# 7_RK3399_MIPI-CSI_I2C.net
KiCad netlist of a schematic drawn in Altium Designer
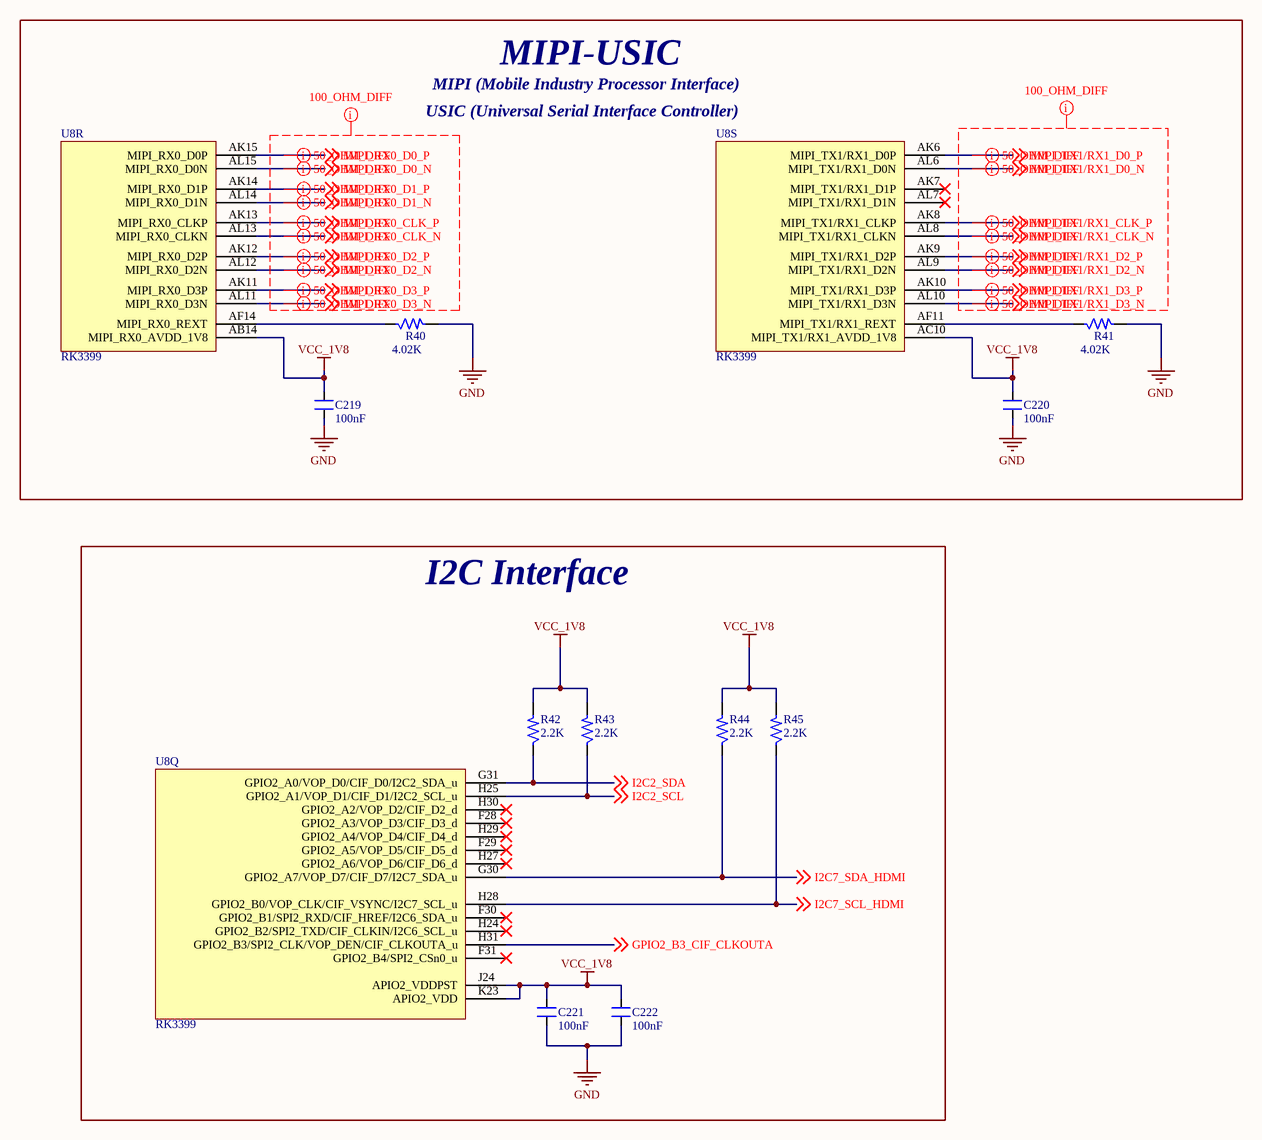
[diagram p0: [7] RK3399_MIPI-CSI_I2C.SchDoc]

(export (version "E")
  (design (tool "Eeschema 10.0.6"))
  (components
    (comp (ref "C219")
      (value "100nF")
      (footprint "CAP_0201")
      (description "0.1µF ±10% 25V Ceramic Capacitor X5R 0201 (0603 Metric)")
      (fields
        (field (name "MANUFACTURER") "TDK Corporation")
        (field (name "MANUFACTURER PART NUMBER") "C0603X5R1E104K030BB")
      )
      (libsource (lib "EsteemPCB_SOM_Course_intlib") (part "CAP_100nF-25V-10%-0201"))
    )
    (comp (ref "C220")
      (value "100nF")
      (footprint "CAP_0201")
      (description "0.1µF ±10% 25V Ceramic Capacitor X5R 0201 (0603 Metric)")
      (fields
        (field (name "MANUFACTURER") "TDK Corporation")
        (field (name "MANUFACTURER PART NUMBER") "C0603X5R1E104K030BB")
      )
      (libsource (lib "EsteemPCB_SOM_Course_intlib") (part "CAP_100nF-25V-10%-0201"))
    )
    (comp (ref "C221")
      (value "100nF")
      (footprint "CAP_0201")
      (description "0.1µF ±10% 25V Ceramic Capacitor X5R 0201 (0603 Metric)")
      (fields
        (field (name "MANUFACTURER") "TDK Corporation")
        (field (name "MANUFACTURER PART NUMBER") "C0603X5R1E104K030BB")
      )
      (libsource (lib "EsteemPCB_SOM_Course_intlib") (part "CAP_100nF-25V-10%-0201"))
    )
    (comp (ref "C222")
      (value "100nF")
      (footprint "CAP_0201")
      (description "0.1µF ±10% 25V Ceramic Capacitor X5R 0201 (0603 Metric)")
      (fields
        (field (name "MANUFACTURER") "TDK Corporation")
        (field (name "MANUFACTURER PART NUMBER") "C0603X5R1E104K030BB")
      )
      (libsource (lib "EsteemPCB_SOM_Course_intlib") (part "CAP_100nF-25V-10%-0201"))
    )
    (comp (ref "R40")
      (value "4.02K")
      (footprint "RES_0201")
      (description "4.02 kOhms ±1% 0.05W, 1/20W Chip Resistor 0201 (0603 Metric) Thick Film")
      (fields
        (field (name "MANUFACTURER") "Yageo")
        (field (name "MANUFACTURER PART NUMBER") "RC0201FR-074K02L")
      )
      (libsource (lib "EsteemPCB_SOM_Course_intlib") (part "RES_4.02K-0.05W-1%-0201"))
    )
    (comp (ref "R41")
      (value "4.02K")
      (footprint "RES_0201")
      (description "4.02 kOhms ±1% 0.05W, 1/20W Chip Resistor 0201 (0603 Metric) Thick Film")
      (fields
        (field (name "MANUFACTURER") "Yageo")
        (field (name "MANUFACTURER PART NUMBER") "RC0201FR-074K02L")
      )
      (libsource (lib "EsteemPCB_SOM_Course_intlib") (part "RES_4.02K-0.05W-1%-0201"))
    )
    (comp (ref "R42")
      (value "2.2K")
      (footprint "RES_0201")
      (description "2.2 kOhms ±1% 0.05W, 1/20W Chip Resistor 0201 (0603 Metric) Thick Film")
      (fields
        (field (name "MANUFACTURER") "Stackpole Electronics Inc")
        (field (name "MANUFACTURER PART NUMBER") "RMCF0201FT2K20")
      )
      (libsource (lib "EsteemPCB_SOM_Course_intlib") (part "RES_2.2K-0.05W-1%-0201"))
    )
    (comp (ref "R43")
      (value "2.2K")
      (footprint "RES_0201")
      (description "2.2 kOhms ±1% 0.05W, 1/20W Chip Resistor 0201 (0603 Metric) Thick Film")
      (fields
        (field (name "MANUFACTURER") "Stackpole Electronics Inc")
        (field (name "MANUFACTURER PART NUMBER") "RMCF0201FT2K20")
      )
      (libsource (lib "EsteemPCB_SOM_Course_intlib") (part "RES_2.2K-0.05W-1%-0201"))
    )
    (comp (ref "R44")
      (value "2.2K")
      (footprint "RES_0201")
      (description "2.2 kOhms ±1% 0.05W, 1/20W Chip Resistor 0201 (0603 Metric) Thick Film")
      (fields
        (field (name "MANUFACTURER") "Stackpole Electronics Inc")
        (field (name "MANUFACTURER PART NUMBER") "RMCF0201FT2K20")
      )
      (libsource (lib "EsteemPCB_SOM_Course_intlib") (part "RES_2.2K-0.05W-1%-0201"))
    )
    (comp (ref "R45")
      (value "2.2K")
      (footprint "RES_0201")
      (description "2.2 kOhms ±1% 0.05W, 1/20W Chip Resistor 0201 (0603 Metric) Thick Film")
      (fields
        (field (name "MANUFACTURER") "Stackpole Electronics Inc")
        (field (name "MANUFACTURER PART NUMBER") "RMCF0201FT2K20")
      )
      (libsource (lib "EsteemPCB_SOM_Course_intlib") (part "RES_2.2K-0.05W-1%-0201"))
    )
    (comp (ref "U8")
      (value "RK3399")
      (footprint "FBGA828_23_826X826")
      (description "RK3399 is a low power, high performance processor for computing, personal mobile.")
      (fields (field (name "MANUFACTURER") "Rockchip"))
      (libsource (lib "EsteemPCB_SOM_Course_intlib") (part "IC_RK3399-FCBGA828"))
    )
  )
  (nets
    (net (code "1") (name "GND") (class "Default")
      (node (ref "C219") (pin "1") (pinfunction "1_1") (pintype "passive"))
      (node (ref "C220") (pin "1") (pinfunction "1_1") (pintype "passive"))
      (node (ref "C221") (pin "1") (pinfunction "1_1") (pintype "passive"))
      (node (ref "C222") (pin "1") (pinfunction "1_1") (pintype "passive"))
      (node (ref "R40") (pin "2") (pinfunction "2_2") (pintype "passive"))
      (node (ref "R41") (pin "2") (pinfunction "2_2") (pintype "passive"))
    )
    (net (code "2") (name "GPIO2_B3_CIF_CLKOUTA") (class "Default")
      (node (ref "U8") (pin "H31") (pinfunction "GPIO2_B3/SPI2_CLK/VOP_DEN/CIF_CLKOUTA_u_H31") (pintype "passive"))
    )
    (net (code "3") (name "I2C2_SCL") (class "Default")
      (node (ref "R43") (pin "1") (pinfunction "1_1") (pintype "passive"))
      (node (ref "U8") (pin "H25") (pinfunction "GPIO2_A1/VOP_D1/CIF_D1/I2C2_SCL_u_H25") (pintype "passive"))
    )
    (net (code "4") (name "I2C2_SDA") (class "Default")
      (node (ref "R42") (pin "1") (pinfunction "1_1") (pintype "passive"))
      (node (ref "U8") (pin "G31") (pinfunction "GPIO2_A0/VOP_D0/CIF_D0/I2C2_SDA_u_G31") (pintype "passive"))
    )
    (net (code "5") (name "I2C7_SCL_HDMI") (class "Default")
      (node (ref "R45") (pin "1") (pinfunction "1_1") (pintype "passive"))
      (node (ref "U8") (pin "H28") (pinfunction "GPIO2_B0/VOP_CLK/CIF_VSYNC/I2C7_SCL_u_H28") (pintype "passive"))
    )
    (net (code "6") (name "I2C7_SDA_HDMI") (class "Default")
      (node (ref "R44") (pin "1") (pinfunction "1_1") (pintype "passive"))
      (node (ref "U8") (pin "G30") (pinfunction "GPIO2_A7/VOP_D7/CIF_D7/I2C7_SDA_u_G30") (pintype "passive"))
    )
    (net (code "7") (name "MIPI_RX0_CLK_N") (class "Default")
      (node (ref "U8") (pin "AL13") (pinfunction "MIPI_RX0_CLKN_AL13") (pintype "passive"))
    )
    (net (code "8") (name "MIPI_RX0_CLK_P") (class "Default")
      (node (ref "U8") (pin "AK13") (pinfunction "MIPI_RX0_CLKP_AK13") (pintype "passive"))
    )
    (net (code "9") (name "MIPI_RX0_D0_N") (class "Default")
      (node (ref "U8") (pin "AL15") (pinfunction "MIPI_RX0_D0N_AL15") (pintype "passive"))
    )
    (net (code "10") (name "MIPI_RX0_D0_P") (class "Default")
      (node (ref "U8") (pin "AK15") (pinfunction "MIPI_RX0_D0P_AK15") (pintype "passive"))
    )
    (net (code "11") (name "MIPI_RX0_D1_N") (class "Default")
      (node (ref "U8") (pin "AL14") (pinfunction "MIPI_RX0_D1N_AL14") (pintype "passive"))
    )
    (net (code "12") (name "MIPI_RX0_D1_P") (class "Default")
      (node (ref "U8") (pin "AK14") (pinfunction "MIPI_RX0_D1P_AK14") (pintype "passive"))
    )
    (net (code "13") (name "MIPI_RX0_D2_N") (class "Default")
      (node (ref "U8") (pin "AL12") (pinfunction "MIPI_RX0_D2N_AL12") (pintype "passive"))
    )
    (net (code "14") (name "MIPI_RX0_D2_P") (class "Default")
      (node (ref "U8") (pin "AK12") (pinfunction "MIPI_RX0_D2P_AK12") (pintype "passive"))
    )
    (net (code "15") (name "MIPI_RX0_D3_N") (class "Default")
      (node (ref "U8") (pin "AL11") (pinfunction "MIPI_RX0_D3N_AL11") (pintype "passive"))
    )
    (net (code "16") (name "MIPI_RX0_D3_P") (class "Default")
      (node (ref "U8") (pin "AK11") (pinfunction "MIPI_RX0_D3P_AK11") (pintype "passive"))
    )
    (net (code "17") (name "MIPI_TX1{slash}RX1_CLK_N") (class "Default")
      (node (ref "U8") (pin "AL8") (pinfunction "MIPI_TX1/RX1_CLKN_AL8") (pintype "passive"))
    )
    (net (code "18") (name "MIPI_TX1{slash}RX1_CLK_P") (class "Default")
      (node (ref "U8") (pin "AK8") (pinfunction "MIPI_TX1/RX1_CLKP_AK8") (pintype "passive"))
    )
    (net (code "19") (name "MIPI_TX1{slash}RX1_D0_N") (class "Default")
      (node (ref "U8") (pin "AL6") (pinfunction "MIPI_TX1/RX1_D0N_AL6") (pintype "passive"))
    )
    (net (code "20") (name "MIPI_TX1{slash}RX1_D0_P") (class "Default")
      (node (ref "U8") (pin "AK6") (pinfunction "MIPI_TX1/RX1_D0P_AK6") (pintype "passive"))
    )
    (net (code "21") (name "MIPI_TX1{slash}RX1_D2_N") (class "Default")
      (node (ref "U8") (pin "AL9") (pinfunction "MIPI_TX1/RX1_D2N_AL9") (pintype "passive"))
    )
    (net (code "22") (name "MIPI_TX1{slash}RX1_D2_P") (class "Default")
      (node (ref "U8") (pin "AK9") (pinfunction "MIPI_TX1/RX1_D2P_AK9") (pintype "passive"))
    )
    (net (code "23") (name "MIPI_TX1{slash}RX1_D3_N") (class "Default")
      (node (ref "U8") (pin "AL10") (pinfunction "MIPI_TX1/RX1_D3N_AL10") (pintype "passive"))
    )
    (net (code "24") (name "MIPI_TX1{slash}RX1_D3_P") (class "Default")
      (node (ref "U8") (pin "AK10") (pinfunction "MIPI_TX1/RX1_D3P_AK10") (pintype "passive"))
    )
    (net (code "25") (name "Net-(U8R-MIPI_RX0_REXT)") (class "Default")
      (node (ref "R40") (pin "1") (pinfunction "1_1") (pintype "passive"))
      (node (ref "U8") (pin "AF14") (pinfunction "MIPI_RX0_REXT_AF14") (pintype "passive"))
    )
    (net (code "26") (name "Net-(U8S-MIPI_TX1{slash}RX1_REXT)") (class "Default")
      (node (ref "R41") (pin "1") (pinfunction "1_1") (pintype "passive"))
      (node (ref "U8") (pin "AF11") (pinfunction "MIPI_TX1/RX1_REXT_AF11") (pintype "passive"))
    )
    (net (code "27") (name "VCC_1V8") (class "Default")
      (node (ref "C219") (pin "2") (pinfunction "2_2") (pintype "passive"))
      (node (ref "C220") (pin "2") (pinfunction "2_2") (pintype "passive"))
      (node (ref "C221") (pin "2") (pinfunction "2_2") (pintype "passive"))
      (node (ref "C222") (pin "2") (pinfunction "2_2") (pintype "passive"))
      (node (ref "R42") (pin "2") (pinfunction "2_2") (pintype "passive"))
      (node (ref "R43") (pin "2") (pinfunction "2_2") (pintype "passive"))
      (node (ref "R44") (pin "2") (pinfunction "2_2") (pintype "passive"))
      (node (ref "R45") (pin "2") (pinfunction "2_2") (pintype "passive"))
      (node (ref "U8") (pin "AB14") (pinfunction "MIPI_RX0_AVDD_1V8_AB14") (pintype "passive"))
      (node (ref "U8") (pin "AC10") (pinfunction "MIPI_TX1/RX1_AVDD_1V8_AC10") (pintype "passive"))
      (node (ref "U8") (pin "J24") (pinfunction "APIO2_VDDPST_J24") (pintype "passive"))
      (node (ref "U8") (pin "K23") (pinfunction "APIO2_VDD_K23") (pintype "passive"))
    )
    (net (code "28") (name "unconnected-(U8Q-GPIO2_A2{slash}VOP_D2{slash}CIF_D2_d-PadH30)") (class "Default")
      (node (ref "U8") (pin "H30") (pinfunction "GPIO2_A2/VOP_D2/CIF_D2_d_H30") (pintype "passive+no_connect"))
    )
    (net (code "29") (name "unconnected-(U8Q-GPIO2_A3{slash}VOP_D3{slash}CIF_D3_d-PadF28)") (class "Default")
      (node (ref "U8") (pin "F28") (pinfunction "GPIO2_A3/VOP_D3/CIF_D3_d_F28") (pintype "passive+no_connect"))
    )
    (net (code "30") (name "unconnected-(U8Q-GPIO2_A4{slash}VOP_D4{slash}CIF_D4_d-PadH29)") (class "Default")
      (node (ref "U8") (pin "H29") (pinfunction "GPIO2_A4/VOP_D4/CIF_D4_d_H29") (pintype "passive+no_connect"))
    )
    (net (code "31") (name "unconnected-(U8Q-GPIO2_A5{slash}VOP_D5{slash}CIF_D5_d-PadF29)") (class "Default")
      (node (ref "U8") (pin "F29") (pinfunction "GPIO2_A5/VOP_D5/CIF_D5_d_F29") (pintype "passive+no_connect"))
    )
    (net (code "32") (name "unconnected-(U8Q-GPIO2_A6{slash}VOP_D6{slash}CIF_D6_d-PadH27)") (class "Default")
      (node (ref "U8") (pin "H27") (pinfunction "GPIO2_A6/VOP_D6/CIF_D6_d_H27") (pintype "passive+no_connect"))
    )
    (net (code "33") (name "unconnected-(U8Q-GPIO2_B1{slash}SPI2_RXD{slash}CIF_HREF{slash}I2C6_SDA_u-PadF30)") (class "Default")
      (node (ref "U8") (pin "F30") (pinfunction "GPIO2_B1/SPI2_RXD/CIF_HREF/I2C6_SDA_u_F30") (pintype "passive+no_connect"))
    )
    (net (code "34") (name "unconnected-(U8Q-GPIO2_B2{slash}SPI2_TXD{slash}CIF_CLKIN{slash}I2C6_SCL_u-PadH24)") (class "Default")
      (node (ref "U8") (pin "H24") (pinfunction "GPIO2_B2/SPI2_TXD/CIF_CLKIN/I2C6_SCL_u_H24") (pintype "passive+no_connect"))
    )
    (net (code "35") (name "unconnected-(U8Q-GPIO2_B4{slash}SPI2_CSn0_u-PadF31)") (class "Default")
      (node (ref "U8") (pin "F31") (pinfunction "GPIO2_B4/SPI2_CSn0_u_F31") (pintype "passive+no_connect"))
    )
    (net (code "36") (name "unconnected-(U8S-MIPI_TX1{slash}RX1_D1N-PadAL7)") (class "Default")
      (node (ref "U8") (pin "AL7") (pinfunction "MIPI_TX1/RX1_D1N_AL7") (pintype "passive+no_connect"))
    )
    (net (code "37") (name "unconnected-(U8S-MIPI_TX1{slash}RX1_D1P-PadAK7)") (class "Default")
      (node (ref "U8") (pin "AK7") (pinfunction "MIPI_TX1/RX1_D1P_AK7") (pintype "passive+no_connect"))
    )
  )
)
